# evalboard.net
KiCad netlist of a schematic drawn in EAGLE
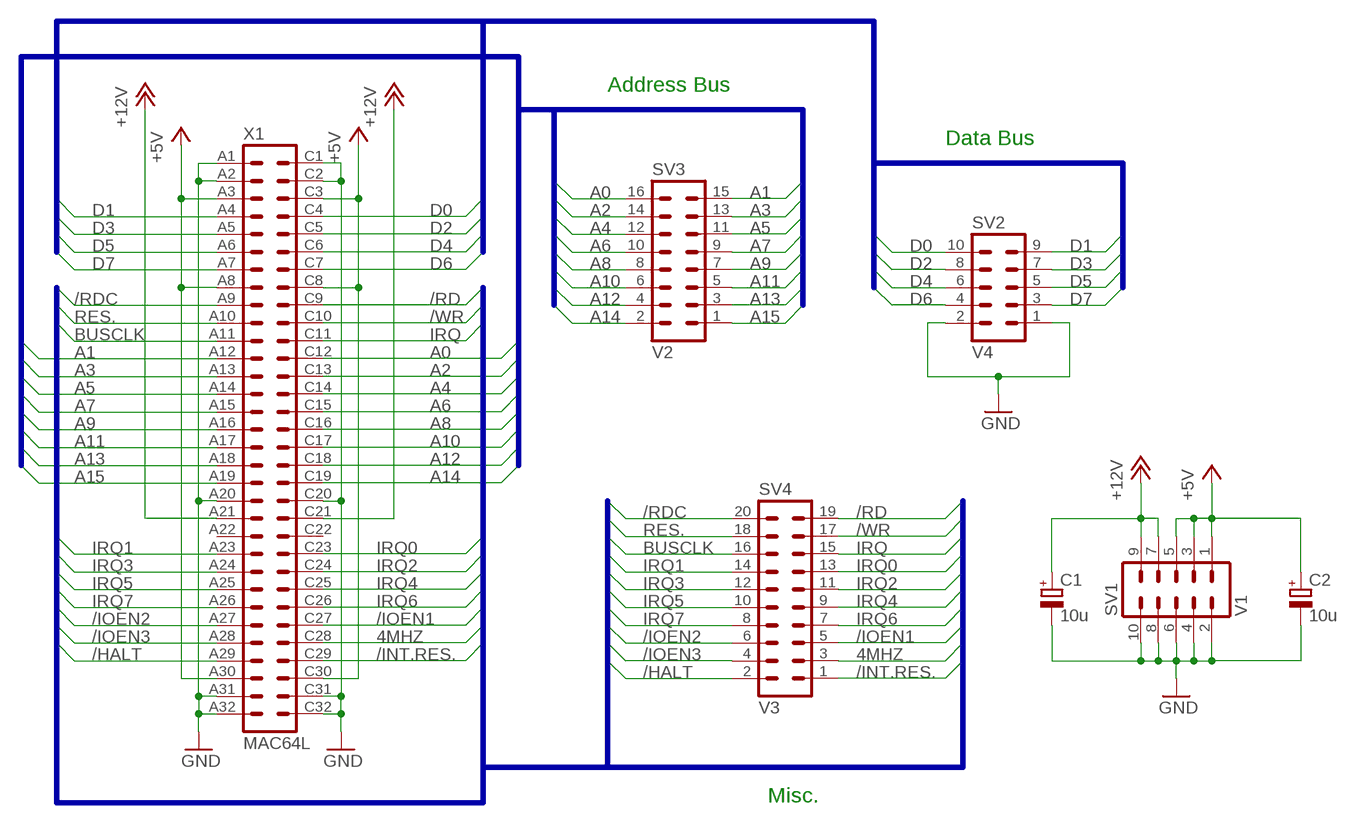
[diagram p0: schematic, sheet 1]

(export (version "E")
  (design (tool "Eeschema 10.0.6"))
  (components
    (comp (ref "C1")
      (value "10u")
      (footprint "eagle-import:E2,5-5")
      (libsource (lib "eagle-import") (part "CPOL-EUE2.5-5"))
    )
    (comp (ref "C2")
      (value "10u")
      (footprint "eagle-import:E2,5-5")
      (libsource (lib "eagle-import") (part "CPOL-EUE2.5-5"))
    )
    (comp (ref "SV1")
      (value "V1")
      (footprint "eagle-import:ML10L")
      (libsource (lib "eagle-import") (part "ML10L"))
    )
    (comp (ref "SV2")
      (value "V4")
      (footprint "eagle-import:ML10L")
      (libsource (lib "eagle-import") (part "ML10L"))
    )
    (comp (ref "SV3")
      (value "V2")
      (footprint "eagle-import:ML16L")
      (libsource (lib "eagle-import") (part "ML16L"))
    )
    (comp (ref "SV4")
      (value "V3")
      (footprint "eagle-import:ML20L")
      (libsource (lib "eagle-import") (part "ML20L"))
    )
    (comp (ref "X1")
      (value "MAC64L")
      (footprint "eagle-import:MAC64L")
      (libsource (lib "eagle-import") (part "MAC64L"))
    )
  )
  (nets
    (net (code "1") (name "+5V") (class "Default")
      (node (ref "C2") (pin "+") (pinfunction "+_+") (pintype "passive"))
      (node (ref "SV1") (pin "1") (pinfunction "1_1") (pintype "passive"))
      (node (ref "SV1") (pin "3") (pinfunction "3_3") (pintype "passive"))
      (node (ref "SV1") (pin "5") (pinfunction "5_5") (pintype "passive"))
      (node (ref "X1") (pin "A3") (pinfunction "A3_A3") (pintype "passive"))
      (node (ref "X1") (pin "A30") (pinfunction "A30_A30") (pintype "passive"))
      (node (ref "X1") (pin "A8") (pinfunction "A8_A8") (pintype "passive"))
      (node (ref "X1") (pin "C3") (pinfunction "C3_C3") (pintype "passive"))
      (node (ref "X1") (pin "C30") (pinfunction "C30_C30") (pintype "passive"))
      (node (ref "X1") (pin "C8") (pinfunction "C8_C8") (pintype "passive"))
    )
    (net (code "2") (name "+12V") (class "Default")
      (node (ref "C1") (pin "+") (pinfunction "+_+") (pintype "passive"))
      (node (ref "SV1") (pin "7") (pinfunction "7_7") (pintype "passive"))
      (node (ref "SV1") (pin "9") (pinfunction "9_9") (pintype "passive"))
      (node (ref "X1") (pin "A21") (pinfunction "A21_A21") (pintype "passive"))
      (node (ref "X1") (pin "C21") (pinfunction "C21_C21") (pintype "passive"))
    )
    (net (code "3") (name "/4MHZ") (class "Default")
      (node (ref "SV4") (pin "3") (pinfunction "3_3") (pintype "passive"))
      (node (ref "X1") (pin "C28") (pinfunction "C28_C28") (pintype "passive"))
    )
    (net (code "4") (name "/A0") (class "Default")
      (node (ref "SV3") (pin "16") (pinfunction "16_16") (pintype "passive"))
      (node (ref "X1") (pin "C12") (pinfunction "C12_C12") (pintype "passive"))
    )
    (net (code "5") (name "/A1") (class "Default")
      (node (ref "SV3") (pin "15") (pinfunction "15_15") (pintype "passive"))
      (node (ref "X1") (pin "A12") (pinfunction "A12_A12") (pintype "passive"))
    )
    (net (code "6") (name "/A2") (class "Default")
      (node (ref "SV3") (pin "14") (pinfunction "14_14") (pintype "passive"))
      (node (ref "X1") (pin "C13") (pinfunction "C13_C13") (pintype "passive"))
    )
    (net (code "7") (name "/A3") (class "Default")
      (node (ref "SV3") (pin "13") (pinfunction "13_13") (pintype "passive"))
      (node (ref "X1") (pin "A13") (pinfunction "A13_A13") (pintype "passive"))
    )
    (net (code "8") (name "/A4") (class "Default")
      (node (ref "SV3") (pin "12") (pinfunction "12_12") (pintype "passive"))
      (node (ref "X1") (pin "C14") (pinfunction "C14_C14") (pintype "passive"))
    )
    (net (code "9") (name "/A5") (class "Default")
      (node (ref "SV3") (pin "11") (pinfunction "11_11") (pintype "passive"))
      (node (ref "X1") (pin "A14") (pinfunction "A14_A14") (pintype "passive"))
    )
    (net (code "10") (name "/A6") (class "Default")
      (node (ref "SV3") (pin "10") (pinfunction "10_10") (pintype "passive"))
      (node (ref "X1") (pin "C15") (pinfunction "C15_C15") (pintype "passive"))
    )
    (net (code "11") (name "/A7") (class "Default")
      (node (ref "SV3") (pin "9") (pinfunction "9_9") (pintype "passive"))
      (node (ref "X1") (pin "A15") (pinfunction "A15_A15") (pintype "passive"))
    )
    (net (code "12") (name "/A8") (class "Default")
      (node (ref "SV3") (pin "8") (pinfunction "8_8") (pintype "passive"))
      (node (ref "X1") (pin "C16") (pinfunction "C16_C16") (pintype "passive"))
    )
    (net (code "13") (name "/A9") (class "Default")
      (node (ref "SV3") (pin "7") (pinfunction "7_7") (pintype "passive"))
      (node (ref "X1") (pin "A16") (pinfunction "A16_A16") (pintype "passive"))
    )
    (net (code "14") (name "/A10") (class "Default")
      (node (ref "SV3") (pin "6") (pinfunction "6_6") (pintype "passive"))
      (node (ref "X1") (pin "C17") (pinfunction "C17_C17") (pintype "passive"))
    )
    (net (code "15") (name "/A11") (class "Default")
      (node (ref "SV3") (pin "5") (pinfunction "5_5") (pintype "passive"))
      (node (ref "X1") (pin "A17") (pinfunction "A17_A17") (pintype "passive"))
    )
    (net (code "16") (name "/A12") (class "Default")
      (node (ref "SV3") (pin "4") (pinfunction "4_4") (pintype "passive"))
      (node (ref "X1") (pin "C18") (pinfunction "C18_C18") (pintype "passive"))
    )
    (net (code "17") (name "/A13") (class "Default")
      (node (ref "SV3") (pin "3") (pinfunction "3_3") (pintype "passive"))
      (node (ref "X1") (pin "A18") (pinfunction "A18_A18") (pintype "passive"))
    )
    (net (code "18") (name "/A14") (class "Default")
      (node (ref "SV3") (pin "2") (pinfunction "2_2") (pintype "passive"))
      (node (ref "X1") (pin "C19") (pinfunction "C19_C19") (pintype "passive"))
    )
    (net (code "19") (name "/A15") (class "Default")
      (node (ref "SV3") (pin "1") (pinfunction "1_1") (pintype "passive"))
      (node (ref "X1") (pin "A19") (pinfunction "A19_A19") (pintype "passive"))
    )
    (net (code "20") (name "/BUSCLK") (class "Default")
      (node (ref "SV4") (pin "16") (pinfunction "16_16") (pintype "passive"))
      (node (ref "X1") (pin "A11") (pinfunction "A11_A11") (pintype "passive"))
    )
    (net (code "21") (name "/D0") (class "Default")
      (node (ref "SV2") (pin "10") (pinfunction "10_10") (pintype "passive"))
      (node (ref "X1") (pin "C4") (pinfunction "C4_C4") (pintype "passive"))
    )
    (net (code "22") (name "/D1") (class "Default")
      (node (ref "SV2") (pin "9") (pinfunction "9_9") (pintype "passive"))
      (node (ref "X1") (pin "A4") (pinfunction "A4_A4") (pintype "passive"))
    )
    (net (code "23") (name "/D2") (class "Default")
      (node (ref "SV2") (pin "8") (pinfunction "8_8") (pintype "passive"))
      (node (ref "X1") (pin "C5") (pinfunction "C5_C5") (pintype "passive"))
    )
    (net (code "24") (name "/D3") (class "Default")
      (node (ref "SV2") (pin "7") (pinfunction "7_7") (pintype "passive"))
      (node (ref "X1") (pin "A5") (pinfunction "A5_A5") (pintype "passive"))
    )
    (net (code "25") (name "/D4") (class "Default")
      (node (ref "SV2") (pin "6") (pinfunction "6_6") (pintype "passive"))
      (node (ref "X1") (pin "C6") (pinfunction "C6_C6") (pintype "passive"))
    )
    (net (code "26") (name "/D5") (class "Default")
      (node (ref "SV2") (pin "5") (pinfunction "5_5") (pintype "passive"))
      (node (ref "X1") (pin "A6") (pinfunction "A6_A6") (pintype "passive"))
    )
    (net (code "27") (name "/D6") (class "Default")
      (node (ref "SV2") (pin "4") (pinfunction "4_4") (pintype "passive"))
      (node (ref "X1") (pin "C7") (pinfunction "C7_C7") (pintype "passive"))
    )
    (net (code "28") (name "/D7") (class "Default")
      (node (ref "SV2") (pin "3") (pinfunction "3_3") (pintype "passive"))
      (node (ref "X1") (pin "A7") (pinfunction "A7_A7") (pintype "passive"))
    )
    (net (code "29") (name "/IRQ") (class "Default")
      (node (ref "SV4") (pin "15") (pinfunction "15_15") (pintype "passive"))
      (node (ref "X1") (pin "C11") (pinfunction "C11_C11") (pintype "passive"))
    )
    (net (code "30") (name "/IRQ0") (class "Default")
      (node (ref "SV4") (pin "13") (pinfunction "13_13") (pintype "passive"))
      (node (ref "X1") (pin "C23") (pinfunction "C23_C23") (pintype "passive"))
    )
    (net (code "31") (name "/IRQ1") (class "Default")
      (node (ref "SV4") (pin "14") (pinfunction "14_14") (pintype "passive"))
      (node (ref "X1") (pin "A23") (pinfunction "A23_A23") (pintype "passive"))
    )
    (net (code "32") (name "/IRQ2") (class "Default")
      (node (ref "SV4") (pin "11") (pinfunction "11_11") (pintype "passive"))
      (node (ref "X1") (pin "C24") (pinfunction "C24_C24") (pintype "passive"))
    )
    (net (code "33") (name "/IRQ3") (class "Default")
      (node (ref "SV4") (pin "12") (pinfunction "12_12") (pintype "passive"))
      (node (ref "X1") (pin "A24") (pinfunction "A24_A24") (pintype "passive"))
    )
    (net (code "34") (name "/IRQ4") (class "Default")
      (node (ref "SV4") (pin "9") (pinfunction "9_9") (pintype "passive"))
      (node (ref "X1") (pin "C25") (pinfunction "C25_C25") (pintype "passive"))
    )
    (net (code "35") (name "/IRQ5") (class "Default")
      (node (ref "SV4") (pin "10") (pinfunction "10_10") (pintype "passive"))
      (node (ref "X1") (pin "A25") (pinfunction "A25_A25") (pintype "passive"))
    )
    (net (code "36") (name "/IRQ6") (class "Default")
      (node (ref "SV4") (pin "7") (pinfunction "7_7") (pintype "passive"))
      (node (ref "X1") (pin "C26") (pinfunction "C26_C26") (pintype "passive"))
    )
    (net (code "37") (name "/IRQ7") (class "Default")
      (node (ref "SV4") (pin "8") (pinfunction "8_8") (pintype "passive"))
      (node (ref "X1") (pin "A26") (pinfunction "A26_A26") (pintype "passive"))
    )
    (net (code "38") (name "/RES.") (class "Default")
      (node (ref "SV4") (pin "18") (pinfunction "18_18") (pintype "passive"))
      (node (ref "X1") (pin "A10") (pinfunction "A10_A10") (pintype "passive"))
    )
    (net (code "39") (name "/{slash}HALT") (class "Default")
      (node (ref "SV4") (pin "2") (pinfunction "2_2") (pintype "passive"))
      (node (ref "X1") (pin "A29") (pinfunction "A29_A29") (pintype "passive"))
    )
    (net (code "40") (name "/{slash}INT.RES.") (class "Default")
      (node (ref "SV4") (pin "1") (pinfunction "1_1") (pintype "passive"))
      (node (ref "X1") (pin "C29") (pinfunction "C29_C29") (pintype "passive"))
    )
    (net (code "41") (name "/{slash}IOEN1") (class "Default")
      (node (ref "SV4") (pin "5") (pinfunction "5_5") (pintype "passive"))
      (node (ref "X1") (pin "C27") (pinfunction "C27_C27") (pintype "passive"))
    )
    (net (code "42") (name "/{slash}IOEN2") (class "Default")
      (node (ref "SV4") (pin "6") (pinfunction "6_6") (pintype "passive"))
      (node (ref "X1") (pin "A27") (pinfunction "A27_A27") (pintype "passive"))
    )
    (net (code "43") (name "/{slash}IOEN3") (class "Default")
      (node (ref "SV4") (pin "4") (pinfunction "4_4") (pintype "passive"))
      (node (ref "X1") (pin "A28") (pinfunction "A28_A28") (pintype "passive"))
    )
    (net (code "44") (name "/{slash}RD") (class "Default")
      (node (ref "SV4") (pin "19") (pinfunction "19_19") (pintype "passive"))
      (node (ref "X1") (pin "C9") (pinfunction "C9_C9") (pintype "passive"))
    )
    (net (code "45") (name "/{slash}RDC") (class "Default")
      (node (ref "SV4") (pin "20") (pinfunction "20_20") (pintype "passive"))
      (node (ref "X1") (pin "A9") (pinfunction "A9_A9") (pintype "passive"))
    )
    (net (code "46") (name "/{slash}WR") (class "Default")
      (node (ref "SV4") (pin "17") (pinfunction "17_17") (pintype "passive"))
      (node (ref "X1") (pin "C10") (pinfunction "C10_C10") (pintype "passive"))
    )
    (net (code "47") (name "GND") (class "Default")
      (node (ref "C1") (pin "-") (pinfunction "-_-") (pintype "passive"))
      (node (ref "C2") (pin "-") (pinfunction "-_-") (pintype "passive"))
      (node (ref "SV1") (pin "10") (pinfunction "10_10") (pintype "passive"))
      (node (ref "SV1") (pin "2") (pinfunction "2_2") (pintype "passive"))
      (node (ref "SV1") (pin "4") (pinfunction "4_4") (pintype "passive"))
      (node (ref "SV1") (pin "6") (pinfunction "6_6") (pintype "passive"))
      (node (ref "SV1") (pin "8") (pinfunction "8_8") (pintype "passive"))
      (node (ref "SV2") (pin "1") (pinfunction "1_1") (pintype "passive"))
      (node (ref "SV2") (pin "2") (pinfunction "2_2") (pintype "passive"))
      (node (ref "X1") (pin "A1") (pinfunction "A1_A1") (pintype "passive"))
      (node (ref "X1") (pin "A2") (pinfunction "A2_A2") (pintype "passive"))
      (node (ref "X1") (pin "A20") (pinfunction "A20_A20") (pintype "passive"))
      (node (ref "X1") (pin "A31") (pinfunction "A31_A31") (pintype "passive"))
      (node (ref "X1") (pin "A32") (pinfunction "A32_A32") (pintype "passive"))
      (node (ref "X1") (pin "C1") (pinfunction "C1_C1") (pintype "passive"))
      (node (ref "X1") (pin "C2") (pinfunction "C2_C2") (pintype "passive"))
      (node (ref "X1") (pin "C20") (pinfunction "C20_C20") (pintype "passive"))
      (node (ref "X1") (pin "C31") (pinfunction "C31_C31") (pintype "passive"))
      (node (ref "X1") (pin "C32") (pinfunction "C32_C32") (pintype "passive"))
    )
    (net (code "48") (name "unconnected-(X1-PadA22)") (class "Default")
      (node (ref "X1") (pin "A22") (pinfunction "A22_A22") (pintype "passive"))
    )
    (net (code "49") (name "unconnected-(X1-PadC22)") (class "Default")
      (node (ref "X1") (pin "C22") (pinfunction "C22_C22") (pintype "passive"))
    )
  )
)
